# PMOD_DPOT.net
KiCad netlist of a schematic drawn in Altium Designer
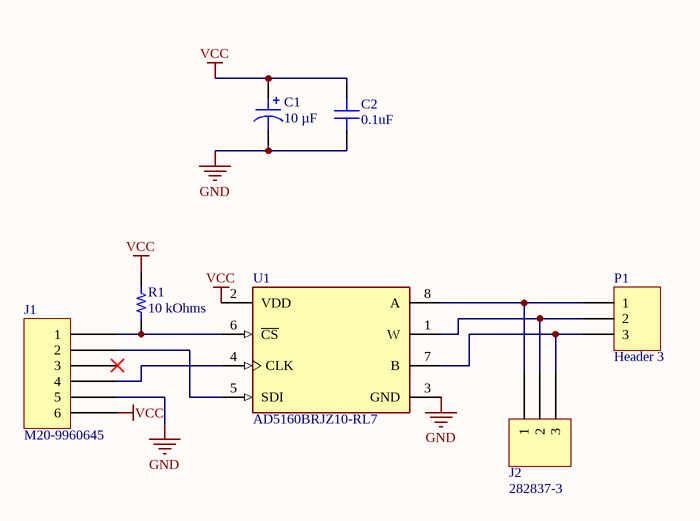
[diagram p0: PMOD_DPOT.SchDoc]

(export (version "E")
  (design (tool "Eeschema 10.0.6"))
  (components
    (comp (ref "C1")
      (value "10 µF")
      (footprint "CAP POL 1411_3528")
      (description "CAP TANT 10UF 20% 16V 1411")
      (fields (field (name "PART NUMBER") "TMCRB1C106MTRF"))
      (libsource (lib "Celestial Altium Library - altium_library") (part "Polarised Capacitor"))
    )
    (comp (ref "C2")
      (value "0.1uF")
      (footprint "CAP 0805_2012")
      (description "CAP CER 10UF 6.3V X7R 0805")
      (fields (field (name "PART NUMBER") "C2012X7R0J106K125AB"))
      (libsource (lib "Celestial Altium Library - altium_library") (part "Capacitor"))
    )
    (comp (ref "J1")
      (value "M20-9960645")
      (footprint "HARWIN M20-9960645")
      (description "CONN HEADER R/A 6POS 2.54MM")
      (libsource (lib "Celestial Altium Library - altium_library") (part "6 Pin"))
    )
    (comp (ref "J2")
      (value "282837-3")
      (footprint "TE 282837-3")
      (description "TERM BLK 3P SIDE ENT 5.08MM PCB")
      (libsource (lib "Celestial Altium Library - altium_library") (part "3 Pin"))
    )
    (comp (ref "P1")
      (value "Header 3")
      (footprint "HDR1X3")
      (description "Header, 3-Pin")
      (fields (field (name "PUBLISHER") "Altium Limited"))
      (libsource (lib "Miscellaneous Connectors") (part "Header 3"))
    )
    (comp (ref "R1")
      (value "10 kOhms")
      (footprint "RES 0805_2012")
      (description "TNPU0805 10K 0.05% 2PPM E52 E3")
      (fields (field (name "PART NUMBER") "TNPU080510K0AWEN00"))
      (libsource (lib "Celestial Altium Library - altium_library") (part "Resistor"))
    )
    (comp (ref "U1")
      (value "AD5160BRJZ10-RL7")
      (footprint "FP-RJ-8-IPC_A")
      (description "IC DGT POT 10KOHM 256TAP SOT23-8")
      (fields (field (name "TOLERANCE") "15%"))
      (libsource (lib "Altium Content Vault") (part "3b375436e07364a1c44378f04b1ac9c"))
    )
  )
  (nets
    (net (code "1") (name "GND") (class "Default")
      (node (ref "C1") (pin "2") (pinfunction "2_2") (pintype "passive"))
      (node (ref "C2") (pin "2") (pinfunction "2_2") (pintype "passive"))
      (node (ref "J1") (pin "5") (pinfunction "5_5") (pintype "passive"))
      (node (ref "U1") (pin "3") (pinfunction "GND_3") (pintype "power_in"))
    )
    (net (code "2") (name "Net-(U1-A)") (class "Default")
      (node (ref "J2") (pin "1") (pinfunction "1_1") (pintype "passive"))
      (node (ref "P1") (pin "1") (pinfunction "1_1") (pintype "passive"))
      (node (ref "U1") (pin "8") (pinfunction "A_8") (pintype "passive"))
    )
    (net (code "3") (name "Net-(U1-B)") (class "Default")
      (node (ref "J2") (pin "3") (pinfunction "3_3") (pintype "passive"))
      (node (ref "P1") (pin "3") (pinfunction "3_3") (pintype "passive"))
      (node (ref "U1") (pin "7") (pinfunction "B_7") (pintype "passive"))
    )
    (net (code "4") (name "Net-(U1-CLK)") (class "Default")
      (node (ref "J1") (pin "4") (pinfunction "4_4") (pintype "passive"))
      (node (ref "U1") (pin "4") (pinfunction "CLK_4") (pintype "input"))
    )
    (net (code "5") (name "Net-(U1-SDI)") (class "Default")
      (node (ref "J1") (pin "2") (pinfunction "2_2") (pintype "passive"))
      (node (ref "U1") (pin "5") (pinfunction "SDI_5") (pintype "input"))
    )
    (net (code "6") (name "Net-(U1-W)") (class "Default")
      (node (ref "J2") (pin "2") (pinfunction "2_2") (pintype "passive"))
      (node (ref "P1") (pin "2") (pinfunction "2_2") (pintype "passive"))
      (node (ref "U1") (pin "1") (pinfunction "W_1") (pintype "passive"))
    )
    (net (code "7") (name "Net-(U1-~{CS})") (class "Default")
      (node (ref "J1") (pin "1") (pinfunction "1_1") (pintype "passive"))
      (node (ref "R1") (pin "1") (pinfunction "1_1") (pintype "passive"))
      (node (ref "U1") (pin "6") (pinfunction "~{CS}_6") (pintype "input"))
    )
    (net (code "8") (name "VCC") (class "Default")
      (node (ref "C1") (pin "1") (pinfunction "1_1") (pintype "passive"))
      (node (ref "C2") (pin "1") (pinfunction "1_1") (pintype "passive"))
      (node (ref "J1") (pin "6") (pinfunction "6_6") (pintype "passive"))
      (node (ref "R1") (pin "2") (pinfunction "2_2") (pintype "passive"))
      (node (ref "U1") (pin "2") (pinfunction "VDD_2") (pintype "power_in"))
    )
    (net (code "9") (name "unconnected-(J1-Pad3)") (class "Default")
      (node (ref "J1") (pin "3") (pinfunction "3_3") (pintype "passive+no_connect"))
    )
  )
)
